# tilt_soms_lgbu_v2.net
KiCad netlist of a schematic drawn in EAGLE
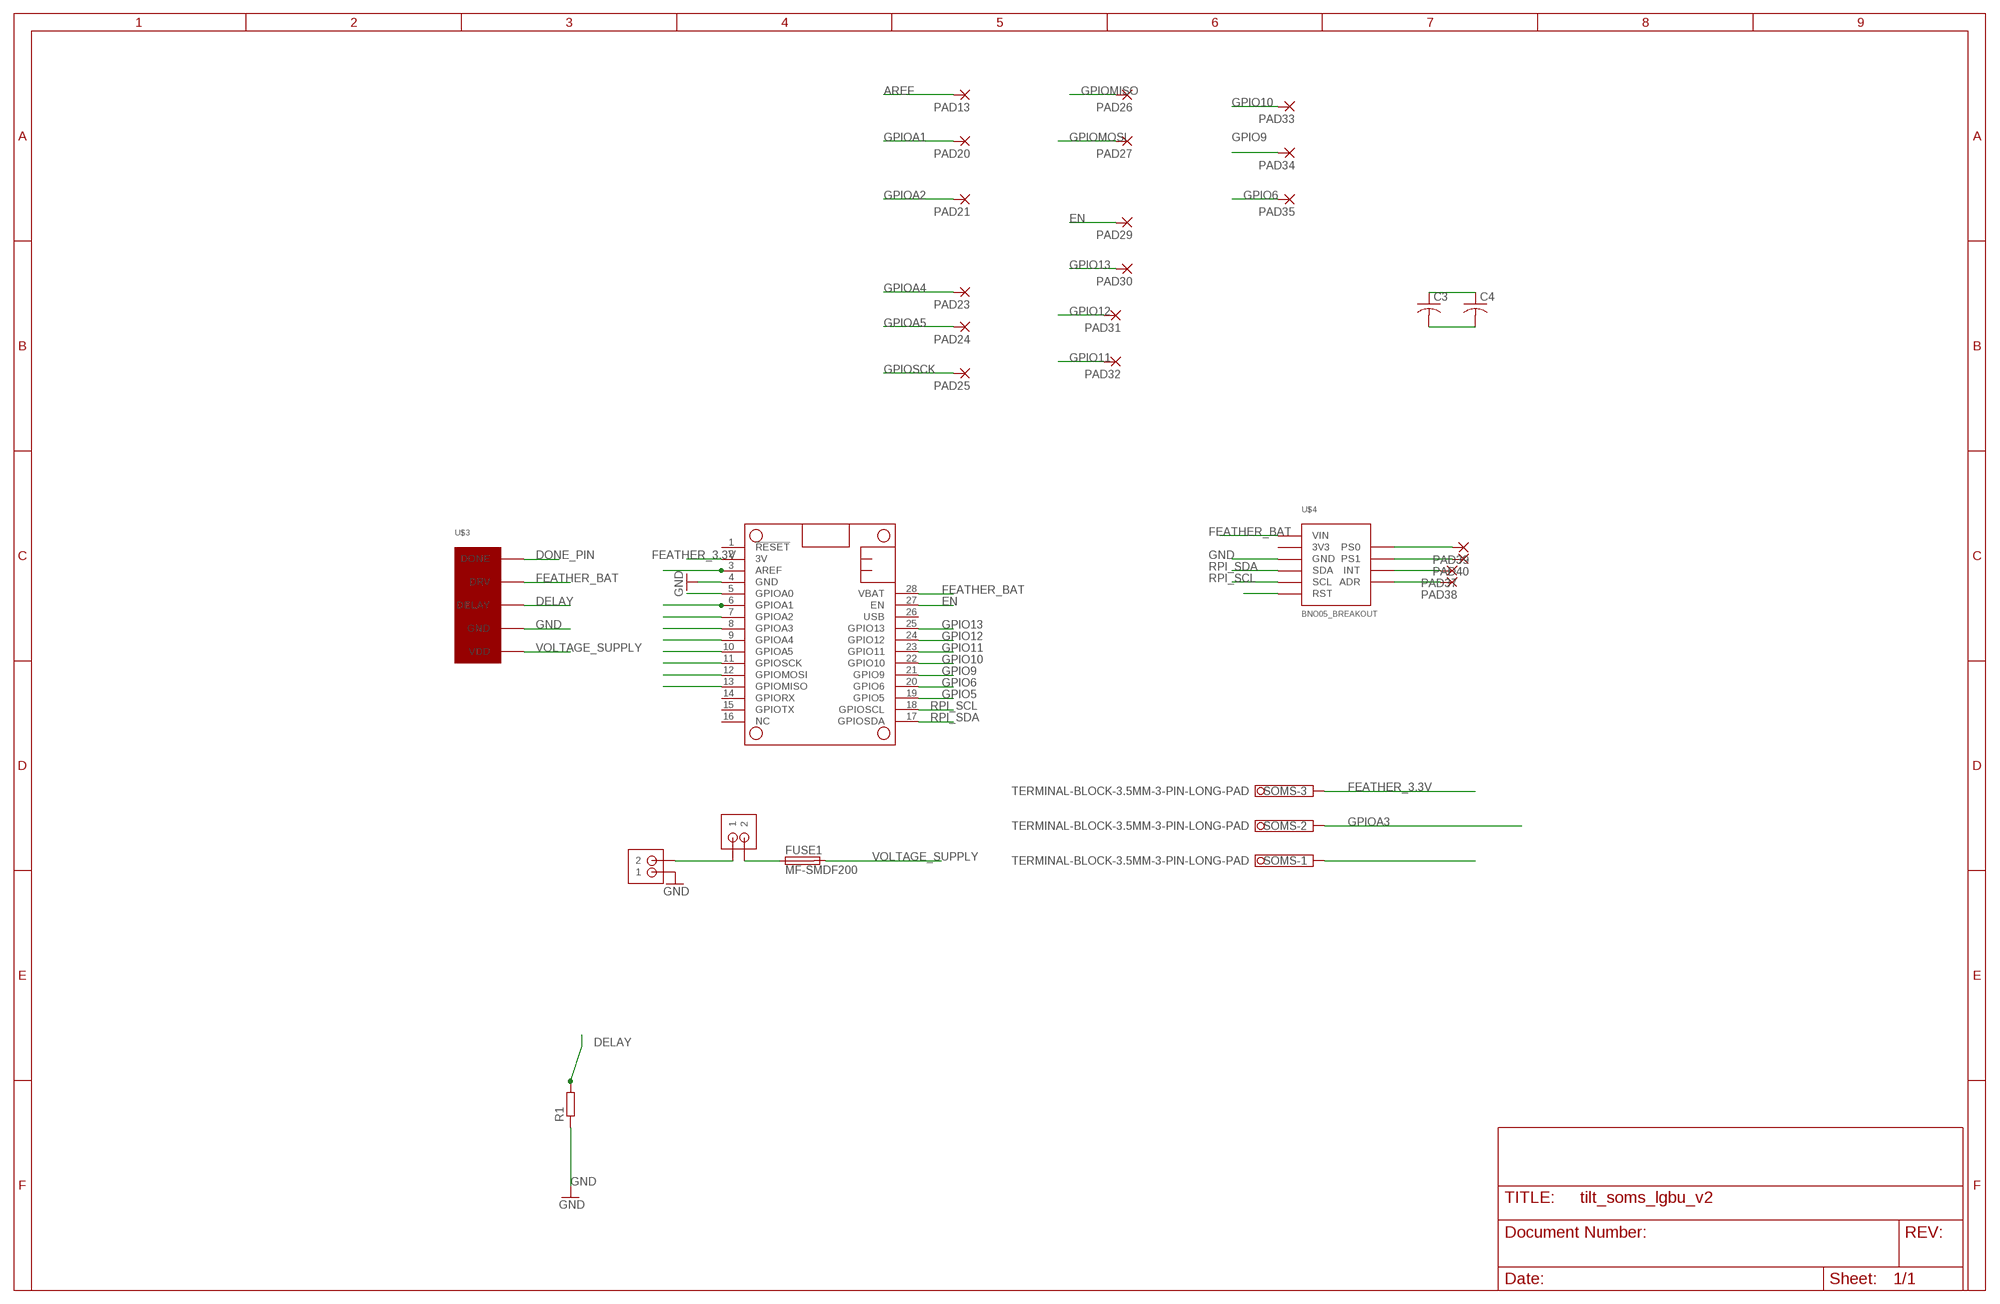
[diagram p0: schematic, sheet 1]

(export (version "E")
  (design (tool "Eeschema 10.0.6"))
  (components
    (comp (ref "BATT")
      (value "JST-PH_2-PIN_HEADER")
      (footprint "eagle-import:JST_B2B-PH_HEADER")
      (libsource (lib "eagle-import") (part "JST-PH_2-PIN_HEADER"))
    )
    (comp (ref "C3")
      (value "C-USC1812")
      (footprint "eagle-import:C1812")
      (libsource (lib "eagle-import") (part "C-USC1812"))
    )
    (comp (ref "C4")
      (value "C-USC1812")
      (footprint "eagle-import:C1812")
      (libsource (lib "eagle-import") (part "C-USC1812"))
    )
    (comp (ref "FUSE1")
      (value "MF-SMDF200")
      (footprint "eagle-import:MF-SMDF050")
      (libsource (lib "eagle-import") (part "MF-SMDF200"))
    )
    (comp (ref "MAIN_SWITCH")
      (value "JST-PH_2-PIN_HEADER")
      (footprint "eagle-import:JST_B2B-PH_HEADER")
      (libsource (lib "eagle-import") (part "JST-PH_2-PIN_HEADER"))
    )
    (comp (ref "MS1")
      (value "FEATHERWING_NODIM")
      (footprint "eagle-import:FEATHERWING_DIM")
      (libsource (lib "eagle-import") (part "FEATHERWING_NODIM"))
    )
    (comp (ref "PAD13")
      (value "WIREPADSMD1,27-254")
      (footprint "eagle-import:SMD1,27-2,54")
      (libsource (lib "eagle-import") (part "WIREPADSMD1,27-254"))
    )
    (comp (ref "PAD20")
      (value "WIREPADSMD1,27-254")
      (footprint "eagle-import:SMD1,27-2,54")
      (libsource (lib "eagle-import") (part "WIREPADSMD1,27-254"))
    )
    (comp (ref "PAD21")
      (value "WIREPADSMD1,27-254")
      (footprint "eagle-import:SMD1,27-2,54")
      (libsource (lib "eagle-import") (part "WIREPADSMD1,27-254"))
    )
    (comp (ref "PAD23")
      (value "WIREPADSMD1,27-254")
      (footprint "eagle-import:SMD1,27-2,54")
      (libsource (lib "eagle-import") (part "WIREPADSMD1,27-254"))
    )
    (comp (ref "PAD24")
      (value "WIREPADSMD1,27-254")
      (footprint "eagle-import:SMD1,27-2,54")
      (libsource (lib "eagle-import") (part "WIREPADSMD1,27-254"))
    )
    (comp (ref "PAD25")
      (value "WIREPADSMD1,27-254")
      (footprint "eagle-import:SMD1,27-2,54")
      (libsource (lib "eagle-import") (part "WIREPADSMD1,27-254"))
    )
    (comp (ref "PAD26")
      (value "WIREPADSMD1,27-254")
      (footprint "eagle-import:SMD1,27-2,54")
      (libsource (lib "eagle-import") (part "WIREPADSMD1,27-254"))
    )
    (comp (ref "PAD27")
      (value "WIREPADSMD1,27-254")
      (footprint "eagle-import:SMD1,27-2,54")
      (libsource (lib "eagle-import") (part "WIREPADSMD1,27-254"))
    )
    (comp (ref "PAD29")
      (value "WIREPADSMD1,27-254")
      (footprint "eagle-import:SMD1,27-2,54")
      (libsource (lib "eagle-import") (part "WIREPADSMD1,27-254"))
    )
    (comp (ref "PAD30")
      (value "WIREPADSMD1,27-254")
      (footprint "eagle-import:SMD1,27-2,54")
      (libsource (lib "eagle-import") (part "WIREPADSMD1,27-254"))
    )
    (comp (ref "PAD31")
      (value "WIREPADSMD1,27-254")
      (footprint "eagle-import:SMD1,27-2,54")
      (libsource (lib "eagle-import") (part "WIREPADSMD1,27-254"))
    )
    (comp (ref "PAD32")
      (value "WIREPADSMD1,27-254")
      (footprint "eagle-import:SMD1,27-2,54")
      (libsource (lib "eagle-import") (part "WIREPADSMD1,27-254"))
    )
    (comp (ref "PAD33")
      (value "WIREPADSMD1,27-254")
      (footprint "eagle-import:SMD1,27-2,54")
      (libsource (lib "eagle-import") (part "WIREPADSMD1,27-254"))
    )
    (comp (ref "PAD34")
      (value "WIREPADSMD1,27-254")
      (footprint "eagle-import:SMD1,27-2,54")
      (libsource (lib "eagle-import") (part "WIREPADSMD1,27-254"))
    )
    (comp (ref "PAD35")
      (value "WIREPADSMD1,27-254")
      (footprint "eagle-import:SMD1,27-2,54")
      (libsource (lib "eagle-import") (part "WIREPADSMD1,27-254"))
    )
    (comp (ref "PAD37")
      (value "WIREPADSMD1,27-254")
      (footprint "eagle-import:SMD1,27-2,54")
      (libsource (lib "eagle-import") (part "WIREPADSMD1,27-254"))
    )
    (comp (ref "PAD38")
      (value "WIREPADSMD1,27-254")
      (footprint "eagle-import:SMD1,27-2,54")
      (libsource (lib "eagle-import") (part "WIREPADSMD1,27-254"))
    )
    (comp (ref "PAD39")
      (value "WIREPADSMD1,27-254")
      (footprint "eagle-import:SMD1,27-2,54")
      (libsource (lib "eagle-import") (part "WIREPADSMD1,27-254"))
    )
    (comp (ref "PAD40")
      (value "WIREPADSMD1,27-254")
      (footprint "eagle-import:SMD1,27-2,54")
      (libsource (lib "eagle-import") (part "WIREPADSMD1,27-254"))
    )
    (comp (ref "R1")
      (value "R-EU_0309/12")
      (footprint "eagle-import:0309_12")
      (libsource (lib "eagle-import") (part "R-EU_0309/12"))
    )
    (comp (ref "SOMS")
      (value "TERMINAL-BLOCK-3.5MM-3-PIN-LONG-PAD")
      (footprint "eagle-import:TERMINAL-BLOCK-3-PIN-3.5MM-LONG-PAD")
      (libsource (lib "eagle-import") (part "TERMINAL-BLOCK-3.5MM-3-PIN-LONG-PAD"))
    )
    (comp (ref "U$3")
      (value "TPL5110_BREAKOUT")
      (footprint "eagle-import:TPL5110_BREAKOUT")
      (libsource (lib "eagle-import") (part "TPL5110_BREAKOUT"))
    )
    (comp (ref "U$4")
      (value "BNO05_BREAKOUT")
      (footprint "eagle-import:BNO05_BREAKOUT")
      (libsource (lib "eagle-import") (part "BNO05_BREAKOUT"))
    )
  )
  (nets
    (net (code "1") (name "/AREF") (class "Default")
      (node (ref "MS1") (pin "3") (pinfunction "AREF_3") (pintype "passive"))
      (node (ref "PAD13") (pin "1") (pinfunction "P_1") (pintype "passive"))
    )
    (net (code "2") (name "/DELAY") (class "Default")
      (node (ref "R1") (pin "2") (pinfunction "2_2") (pintype "passive"))
      (node (ref "U$3") (pin "DELAY") (pinfunction "DELAY_DELAY") (pintype "bidirectional"))
    )
    (net (code "3") (name "/DONE_PIN") (class "Default")
      (node (ref "MS1") (pin "5") (pinfunction "GPIOA0_5") (pintype "bidirectional"))
      (node (ref "U$3") (pin "DONE") (pinfunction "DONE_DONE") (pintype "bidirectional"))
    )
    (net (code "4") (name "/EN") (class "Default")
      (node (ref "MS1") (pin "27") (pinfunction "EN_27") (pintype "passive"))
      (node (ref "PAD29") (pin "1") (pinfunction "P_1") (pintype "passive"))
    )
    (net (code "5") (name "/FEATHER_3.3V") (class "Default")
      (node (ref "MS1") (pin "2") (pinfunction "3V_2") (pintype "power_in"))
      (node (ref "SOMS") (pin "3") (pinfunction "K_3") (pintype "passive"))
    )
    (net (code "6") (name "/FEATHER_BAT") (class "Default")
      (node (ref "MS1") (pin "28") (pinfunction "VBAT_28") (pintype "power_in"))
      (node (ref "U$3") (pin "DRV") (pinfunction "DRV_DRV") (pintype "power_in"))
      (node (ref "U$4") (pin "VIN") (pinfunction "VIN_VIN") (pintype "power_in"))
    )
    (net (code "7") (name "/GPIO5") (class "Default")
      (node (ref "MS1") (pin "19") (pinfunction "GPIO5_19") (pintype "bidirectional"))
      (node (ref "U$4") (pin "RST") (pinfunction "RST_RST") (pintype "bidirectional"))
    )
    (net (code "8") (name "/GPIO6") (class "Default")
      (node (ref "MS1") (pin "20") (pinfunction "GPIO6_20") (pintype "bidirectional"))
      (node (ref "PAD35") (pin "1") (pinfunction "P_1") (pintype "passive"))
    )
    (net (code "9") (name "/GPIO9") (class "Default")
      (node (ref "MS1") (pin "21") (pinfunction "GPIO9_21") (pintype "bidirectional"))
      (node (ref "PAD34") (pin "1") (pinfunction "P_1") (pintype "passive"))
    )
    (net (code "10") (name "/GPIO10") (class "Default")
      (node (ref "MS1") (pin "22") (pinfunction "GPIO10_22") (pintype "bidirectional"))
      (node (ref "PAD33") (pin "1") (pinfunction "P_1") (pintype "passive"))
    )
    (net (code "11") (name "/GPIO11") (class "Default")
      (node (ref "MS1") (pin "23") (pinfunction "GPIO11_23") (pintype "bidirectional"))
      (node (ref "PAD32") (pin "1") (pinfunction "P_1") (pintype "passive"))
    )
    (net (code "12") (name "/GPIO12") (class "Default")
      (node (ref "MS1") (pin "24") (pinfunction "GPIO12_24") (pintype "bidirectional"))
      (node (ref "PAD31") (pin "1") (pinfunction "P_1") (pintype "passive"))
    )
    (net (code "13") (name "/GPIO13") (class "Default")
      (node (ref "MS1") (pin "25") (pinfunction "GPIO13_25") (pintype "bidirectional"))
      (node (ref "PAD30") (pin "1") (pinfunction "P_1") (pintype "passive"))
    )
    (net (code "14") (name "/GPIOA1") (class "Default")
      (node (ref "MS1") (pin "6") (pinfunction "GPIOA1_6") (pintype "bidirectional"))
      (node (ref "PAD20") (pin "1") (pinfunction "P_1") (pintype "passive"))
    )
    (net (code "15") (name "/GPIOA2") (class "Default")
      (node (ref "MS1") (pin "7") (pinfunction "GPIOA2_7") (pintype "bidirectional"))
      (node (ref "PAD21") (pin "1") (pinfunction "P_1") (pintype "passive"))
    )
    (net (code "16") (name "/GPIOA3") (class "Default")
      (node (ref "MS1") (pin "8") (pinfunction "GPIOA3_8") (pintype "bidirectional"))
      (node (ref "SOMS") (pin "2") (pinfunction "K_2") (pintype "passive"))
    )
    (net (code "17") (name "/GPIOA4") (class "Default")
      (node (ref "MS1") (pin "9") (pinfunction "GPIOA4_9") (pintype "bidirectional"))
      (node (ref "PAD23") (pin "1") (pinfunction "P_1") (pintype "passive"))
    )
    (net (code "18") (name "/GPIOA5") (class "Default")
      (node (ref "MS1") (pin "10") (pinfunction "GPIOA5_10") (pintype "bidirectional"))
      (node (ref "PAD24") (pin "1") (pinfunction "P_1") (pintype "passive"))
    )
    (net (code "19") (name "/GPIOMISO") (class "Default")
      (node (ref "MS1") (pin "13") (pinfunction "GPIOMISO_13") (pintype "bidirectional"))
      (node (ref "PAD26") (pin "1") (pinfunction "P_1") (pintype "passive"))
    )
    (net (code "20") (name "/GPIOMOSI") (class "Default")
      (node (ref "MS1") (pin "12") (pinfunction "GPIOMOSI_12") (pintype "bidirectional"))
      (node (ref "PAD27") (pin "1") (pinfunction "P_1") (pintype "passive"))
    )
    (net (code "21") (name "/GPIOSCK") (class "Default")
      (node (ref "MS1") (pin "11") (pinfunction "GPIOSCK_11") (pintype "bidirectional"))
      (node (ref "PAD25") (pin "1") (pinfunction "P_1") (pintype "passive"))
    )
    (net (code "22") (name "/RPI_SCL") (class "Default")
      (node (ref "MS1") (pin "18") (pinfunction "GPIOSCL_18") (pintype "bidirectional"))
      (node (ref "U$4") (pin "SCL") (pinfunction "SCL_SCL") (pintype "bidirectional"))
    )
    (net (code "23") (name "/RPI_SDA") (class "Default")
      (node (ref "MS1") (pin "17") (pinfunction "GPIOSDA_17") (pintype "bidirectional"))
      (node (ref "U$4") (pin "SDA") (pinfunction "SDA_SDA") (pintype "bidirectional"))
    )
    (net (code "24") (name "/USB") (class "Default")
      (node (ref "MS1") (pin "26") (pinfunction "USB_26") (pintype "power_in"))
    )
    (net (code "25") (name "/VOLTAGE_SUPPLY") (class "Default")
      (node (ref "C3") (pin "1") (pinfunction "1_1") (pintype "passive"))
      (node (ref "C4") (pin "1") (pinfunction "1_1") (pintype "passive"))
      (node (ref "FUSE1") (pin "2") (pinfunction "2_2") (pintype "passive"))
      (node (ref "U$3") (pin "VDD") (pinfunction "VDD_VDD") (pintype "power_in"))
    )
    (net (code "26") (name "GND") (class "Default")
      (node (ref "BATT") (pin "P1") (pinfunction "1_P1") (pintype "bidirectional"))
      (node (ref "C3") (pin "2") (pinfunction "2_2") (pintype "passive"))
      (node (ref "C4") (pin "2") (pinfunction "2_2") (pintype "passive"))
      (node (ref "MS1") (pin "4") (pinfunction "GND_4") (pintype "power_in"))
      (node (ref "R1") (pin "1") (pinfunction "1_1") (pintype "passive"))
      (node (ref "SOMS") (pin "1") (pinfunction "K_1") (pintype "passive"))
      (node (ref "U$3") (pin "GND") (pinfunction "GND_GND") (pintype "power_in"))
      (node (ref "U$4") (pin "GND") (pinfunction "GND_GND") (pintype "bidirectional"))
    )
    (net (code "27") (name "Net-(BATT-2)") (class "Default")
      (node (ref "BATT") (pin "P2") (pinfunction "2_P2") (pintype "bidirectional"))
      (node (ref "MAIN_SWITCH") (pin "P1") (pinfunction "1_P1") (pintype "bidirectional"))
    )
    (net (code "28") (name "Net-(MAIN_SWITCH-2)") (class "Default")
      (node (ref "FUSE1") (pin "1") (pinfunction "1_1") (pintype "passive"))
      (node (ref "MAIN_SWITCH") (pin "P2") (pinfunction "2_P2") (pintype "bidirectional"))
    )
    (net (code "29") (name "Net-(PAD37-P)") (class "Default")
      (node (ref "PAD37") (pin "1") (pinfunction "P_1") (pintype "passive"))
      (node (ref "U$4") (pin "INT") (pinfunction "INT_INT") (pintype "bidirectional"))
    )
    (net (code "30") (name "Net-(PAD38-P)") (class "Default")
      (node (ref "PAD38") (pin "1") (pinfunction "P_1") (pintype "passive"))
      (node (ref "U$4") (pin "ADR") (pinfunction "ADR_ADR") (pintype "bidirectional"))
    )
    (net (code "31") (name "Net-(PAD39-P)") (class "Default")
      (node (ref "PAD39") (pin "1") (pinfunction "P_1") (pintype "passive"))
      (node (ref "U$4") (pin "PS0") (pinfunction "PS0_PS0") (pintype "bidirectional"))
    )
    (net (code "32") (name "Net-(PAD40-P)") (class "Default")
      (node (ref "PAD40") (pin "1") (pinfunction "P_1") (pintype "passive"))
      (node (ref "U$4") (pin "PS1") (pinfunction "PS1_PS1") (pintype "bidirectional"))
    )
    (net (code "33") (name "unconnected-(MS1-GPIORX-Pad14)") (class "Default")
      (node (ref "MS1") (pin "14") (pinfunction "GPIORX_14") (pintype "bidirectional"))
    )
    (net (code "34") (name "unconnected-(MS1-GPIOTX-Pad15)") (class "Default")
      (node (ref "MS1") (pin "15") (pinfunction "GPIOTX_15") (pintype "bidirectional"))
    )
    (net (code "35") (name "unconnected-(MS1-NC-Pad16)") (class "Default")
      (node (ref "MS1") (pin "16") (pinfunction "NC_16") (pintype "passive"))
    )
    (net (code "36") (name "unconnected-(MS1-~{RESET}-Pad1)") (class "Default")
      (node (ref "MS1") (pin "1") (pinfunction "~{RESET}_1") (pintype "input"))
    )
    (net (code "37") (name "unconnected-(U$4-Pad3V3)") (class "Default")
      (node (ref "U$4") (pin "3V3") (pinfunction "3V3_3V3") (pintype "bidirectional"))
    )
  )
)
